# CurrentSource.net
KiCad netlist of a schematic drawn in Altium Designer
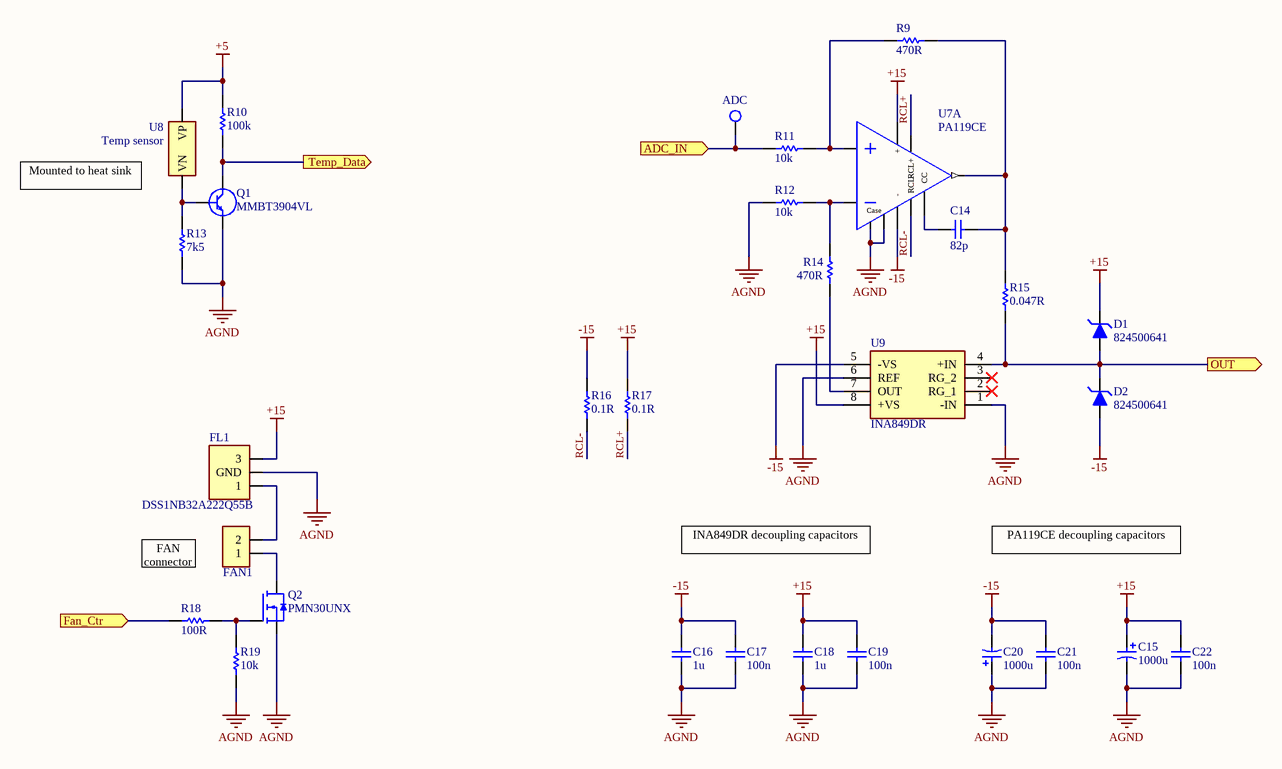
[diagram p0: CurrentSource.SchDoc]

(export (version "E")
  (design (tool "Eeschema 10.0.6"))
  (components
    (comp (ref "C14")
      (value "82p")
      (footprint "Cap_0603_MD_outline")
      (description "Capacitor")
      (fields (field (name "MPN") "GQM1875C2E820JB12D"))
      (libsource (lib "LibPassive") (part "Capacitor"))
    )
    (comp (ref "C15")
      (value "1000u")
      (footprint "CAPAE1350X1400N")
      (description "Aluminium Electrolytic Capacitor")
      (fields (field (name "MPN") "EEE-FK1E102AQ"))
      (libsource (lib "LibPassive") (part "Capacitor Electrolytic"))
    )
    (comp (ref "C16")
      (value "1u")
      (footprint "Cap_0805_MD_outline")
      (description "Capacitor")
      (fields (field (name "MPN") "GCJ21BR71H105KA01L"))
      (libsource (lib "LibPassive") (part "Capacitor"))
    )
    (comp (ref "C17")
      (value "100n")
      (footprint "Cap_0603_MD_outline")
      (description "Capacitor")
      (fields (field (name "MPN") "GRM188R72A104KA35"))
      (libsource (lib "LibPassive") (part "Capacitor"))
    )
    (comp (ref "C18")
      (value "1u")
      (footprint "Cap_0805_MD_outline")
      (description "Capacitor")
      (fields (field (name "MPN") "GCJ21BR71H105KA01L"))
      (libsource (lib "LibPassive") (part "Capacitor"))
    )
    (comp (ref "C19")
      (value "100n")
      (footprint "Cap_0603_MD_outline")
      (description "Capacitor")
      (fields (field (name "MPN") "GRM188R72A104KA35"))
      (libsource (lib "LibPassive") (part "Capacitor"))
    )
    (comp (ref "C20")
      (value "1000u")
      (footprint "CAPAE1350X1400N")
      (description "Aluminium Electrolytic Capacitor")
      (fields (field (name "MPN") "EEE-FK1E102AQ"))
      (libsource (lib "LibPassive") (part "Capacitor Electrolytic"))
    )
    (comp (ref "C21")
      (value "100n")
      (footprint "Cap_0603_MD_outline")
      (description "Capacitor")
      (fields (field (name "MPN") "GRM188R72A104KA35"))
      (libsource (lib "LibPassive") (part "Capacitor"))
    )
    (comp (ref "C22")
      (value "100n")
      (footprint "Cap_0603_MD_outline")
      (description "Capacitor")
      (fields (field (name "MPN") "GRM188R72A104KA35"))
      (libsource (lib "LibPassive") (part "Capacitor"))
    )
    (comp (ref "D1")
      (value "824500641")
      (footprint "DIOM5127X250N")
      (description "TVS Diode")
      (libsource (lib "Library") (part "824500641"))
    )
    (comp (ref "D2")
      (value "824500641")
      (footprint "DIOM5127X250N")
      (description "TVS Diode")
      (libsource (lib "Library") (part "824500641"))
    )
    (comp (ref "FAN1")
      (value "~")
      (footprint "Pads_2")
      (description "2 Pads")
      (libsource (lib "Schlib") (part "Pads_2"))
    )
    (comp (ref "FL1")
      (value "DSS1NB32A222Q55B")
      (footprint "DSS1NB32A223Q91A")
      (description "EMIFilter")
      (libsource (lib "Library") (part "DSS1NB32A222Q55B"))
    )
    (comp (ref "Q1")
      (value "MMBT3904VL")
      (footprint "SOT95P230X110-3N")
      (description "Transistor BJT NPN")
      (libsource (lib "Library") (part "MMBT3904VL"))
    )
    (comp (ref "Q2")
      (value "PMN30UNX")
      (footprint "SOT95P275X110-6N")
      (description "Transistor MOSFET N-Channel")
      (libsource (lib "Schlib") (part "PMN30UNX"))
    )
    (comp (ref "R9")
      (value "470R")
      (footprint "Res_0603_MD_outline")
      (description "Resistor")
      (fields (field (name "MPN") "MCT0603MD4700BP100"))
      (libsource (lib "LibPassive") (part "Resistor"))
    )
    (comp (ref "R10")
      (value "100k")
      (footprint "Res_0603_MD_outline")
      (description "Resistor")
      (fields (field (name "MPN") "CRCW0603100KFKEAC"))
      (libsource (lib "LibPassive") (part "Resistor"))
    )
    (comp (ref "R11")
      (value "10k")
      (footprint "Res_0603_MD_outline")
      (description "Resistor")
      (fields (field (name "MPN") "MCT06030E1002BP100"))
      (libsource (lib "LibPassive") (part "Resistor"))
    )
    (comp (ref "R12")
      (value "10k")
      (footprint "Res_0603_MD_outline")
      (description "Resistor")
      (fields (field (name "MPN") "MCT06030E1002BP100"))
      (libsource (lib "LibPassive") (part "Resistor"))
    )
    (comp (ref "R13")
      (value "7k5")
      (footprint "Res_0603_MD_outline")
      (description "Resistor")
      (fields (field (name "MPN") "CRCW06037K50FKEA"))
      (libsource (lib "LibPassive") (part "Resistor"))
    )
    (comp (ref "R14")
      (value "470R")
      (footprint "Res_0603_MD_outline")
      (description "Resistor")
      (fields (field (name "MPN") "MCT0603MD4700BP100"))
      (libsource (lib "LibPassive") (part "Resistor"))
    )
    (comp (ref "R15")
      (value "0.047R")
      (footprint "Res_2512")
      (description "Resistor")
      (fields (field (name "MPN") "GMR100HTBFQR047"))
      (libsource (lib "LibPassive") (part "Shunt"))
    )
    (comp (ref "R16")
      (value "0.1R")
      (footprint "Res_0603_MD_outline")
      (description "Resistor")
      (fields (field (name "MPN") "RCWE0603R100FNEA"))
      (libsource (lib "LibPassive") (part "Resistor"))
    )
    (comp (ref "R17")
      (value "0.1R")
      (footprint "Res_0603_MD_outline")
      (description "Resistor")
      (fields (field (name "MPN") "RCWE0603R100FNEA"))
      (libsource (lib "LibPassive") (part "Resistor"))
    )
    (comp (ref "R18")
      (value "100R")
      (footprint "Res_0603_MD_outline")
      (description "Resistor")
      (fields (field (name "MPN") "CRCW0603100RFKEAHP"))
      (libsource (lib "LibPassive") (part "Resistor"))
    )
    (comp (ref "R19")
      (value "10k")
      (footprint "Res_0603_MD_outline")
      (description "Resistor")
      (fields (field (name "MPN") "CRCW060310K0FKEAC"))
      (libsource (lib "LibPassive") (part "Resistor"))
    )
    (comp (ref "TP8")
      (value "ADC")
      (footprint "TP_SQ40")
      (description "Test point")
      (libsource (lib "Library") (part "TestPoint"))
    )
    (comp (ref "U7")
      (value "PA119CE")
      (footprint "PA119CE")
      (description "Op Amp")
      (libsource (lib "Library") (part "PA119CE"))
    )
    (comp (ref "U8")
      (value "Temp sensor")
      (footprint "TO-92S")
      (description "Temperature sensor, Pulse Train Interface")
      (fields (field (name "MPN") "LMT01LPGM"))
      (libsource (lib "Schlib") (part "LMT01LPGM"))
    )
    (comp (ref "U9")
      (value "INA849DR")
      (footprint "SOIC127P600X175-8N")
      (description "Instrumental Amplifier")
      (libsource (lib "Library") (part "INA849DR"))
    )
  )
  (nets
    (net (code "1") (name "+5") (class "Default")
      (node (ref "R10") (pin "2") (pinfunction "2_2") (pintype "passive"))
      (node (ref "U8") (pin "2") (pinfunction "VP_2") (pintype "passive"))
    )
    (net (code "2") (name "+15") (class "Default")
      (node (ref "C15") (pin "1") (pinfunction "1_1") (pintype "passive"))
      (node (ref "C18") (pin "2") (pinfunction "2_2") (pintype "passive"))
      (node (ref "C19") (pin "2") (pinfunction "2_2") (pintype "passive"))
      (node (ref "C22") (pin "2") (pinfunction "2_2") (pintype "passive"))
      (node (ref "D1") (pin "1") (pinfunction "K_1") (pintype "passive"))
      (node (ref "FL1") (pin "3") (pinfunction "3_3") (pintype "passive"))
      (node (ref "R17") (pin "2") (pinfunction "2_2") (pintype "passive"))
      (node (ref "U7") (pin "3") (pinfunction "+_3") (pintype "passive"))
      (node (ref "U9") (pin "8") (pinfunction "+VS_8") (pintype "passive"))
    )
    (net (code "3") (name "-15") (class "Default")
      (node (ref "C16") (pin "2") (pinfunction "2_2") (pintype "passive"))
      (node (ref "C17") (pin "2") (pinfunction "2_2") (pintype "passive"))
      (node (ref "C20") (pin "2") (pinfunction "2_2") (pintype "passive"))
      (node (ref "C21") (pin "2") (pinfunction "2_2") (pintype "passive"))
      (node (ref "D2") (pin "2") (pinfunction "A_2") (pintype "passive"))
      (node (ref "R16") (pin "2") (pinfunction "2_2") (pintype "passive"))
      (node (ref "U7") (pin "6") (pinfunction "-_6") (pintype "passive"))
      (node (ref "U9") (pin "5") (pinfunction "-VS_5") (pintype "passive"))
    )
    (net (code "4") (name "/ADC_IN") (class "Default")
      (node (ref "R11") (pin "1") (pinfunction "1_1") (pintype "passive"))
      (node (ref "TP8") (pin "1") (pintype "passive"))
    )
    (net (code "5") (name "/Fan_Ctr") (class "Default")
      (node (ref "R18") (pin "2") (pinfunction "2_2") (pintype "passive"))
    )
    (net (code "6") (name "/OUT") (class "Default")
      (node (ref "D1") (pin "2") (pinfunction "A_2") (pintype "passive"))
      (node (ref "D2") (pin "1") (pinfunction "K_1") (pintype "passive"))
      (node (ref "R15") (pin "1") (pinfunction "1_1") (pintype "passive"))
      (node (ref "U9") (pin "4") (pinfunction "+IN_4") (pintype "passive"))
    )
    (net (code "7") (name "/RCL+") (class "Default")
      (node (ref "R17") (pin "1") (pinfunction "1_1") (pintype "passive"))
      (node (ref "U7") (pin "2") (pinfunction "RCL+_2") (pintype "passive"))
    )
    (net (code "8") (name "/RCL-") (class "Default")
      (node (ref "R16") (pin "1") (pinfunction "1_1") (pintype "passive"))
      (node (ref "U7") (pin "7") (pinfunction "RCL-_7") (pintype "passive"))
    )
    (net (code "9") (name "/Temp_Data") (class "Default")
      (node (ref "Q1") (pin "3") (pinfunction "C_3") (pintype "passive"))
      (node (ref "R10") (pin "1") (pinfunction "1_1") (pintype "passive"))
    )
    (net (code "10") (name "AGND") (class "Default")
      (node (ref "C15") (pin "2") (pinfunction "2_2") (pintype "passive"))
      (node (ref "C16") (pin "1") (pinfunction "1_1") (pintype "passive"))
      (node (ref "C17") (pin "1") (pinfunction "1_1") (pintype "passive"))
      (node (ref "C18") (pin "1") (pinfunction "1_1") (pintype "passive"))
      (node (ref "C19") (pin "1") (pinfunction "1_1") (pintype "passive"))
      (node (ref "C20") (pin "1") (pinfunction "1_1") (pintype "passive"))
      (node (ref "C21") (pin "1") (pinfunction "1_1") (pintype "passive"))
      (node (ref "C22") (pin "1") (pinfunction "1_1") (pintype "passive"))
      (node (ref "FL1") (pin "2") (pinfunction "GND_2") (pintype "passive"))
      (node (ref "Q1") (pin "2") (pinfunction "E_2") (pintype "passive"))
      (node (ref "Q2") (pin "4") (pinfunction "S_4") (pintype "passive"))
      (node (ref "R12") (pin "1") (pinfunction "1_1") (pintype "passive"))
      (node (ref "R13") (pin "1") (pinfunction "1_1") (pintype "passive"))
      (node (ref "R19") (pin "1") (pinfunction "1_1") (pintype "passive"))
      (node (ref "U7") (pin "MH1") (pinfunction "MH1_MH1") (pintype "passive"))
      (node (ref "U7") (pin "MH2") (pinfunction "MH2_MH2") (pintype "passive"))
      (node (ref "U9") (pin "1") (pinfunction "-IN_1") (pintype "passive"))
      (node (ref "U9") (pin "6") (pinfunction "REF_6") (pintype "passive"))
    )
    (net (code "11") (name "Net-(FAN1-Pad2)") (class "Default")
      (node (ref "FAN1") (pin "2") (pinfunction "2_2") (pintype "passive"))
      (node (ref "FL1") (pin "1") (pinfunction "1_1") (pintype "passive"))
    )
    (net (code "12") (name "Net-(Q1-B)") (class "Default")
      (node (ref "Q1") (pin "1") (pinfunction "B_1") (pintype "passive"))
      (node (ref "R13") (pin "2") (pinfunction "2_2") (pintype "passive"))
      (node (ref "U8") (pin "1") (pinfunction "VN_1") (pintype "passive"))
    )
    (net (code "13") (name "Net-(Q2-D)") (class "Default")
      (node (ref "FAN1") (pin "1") (pinfunction "1_1") (pintype "passive"))
      (node (ref "Q2") (pin "1") (pinfunction "D_1") (pintype "passive"))
    )
    (net (code "14") (name "Net-(Q2-G)") (class "Default")
      (node (ref "Q2") (pin "3") (pinfunction "G_3") (pintype "passive"))
      (node (ref "R18") (pin "1") (pinfunction "1_1") (pintype "passive"))
      (node (ref "R19") (pin "2") (pinfunction "2_2") (pintype "passive"))
    )
    (net (code "15") (name "Net-(U7A-+IN)") (class "Default")
      (node (ref "R11") (pin "2") (pinfunction "2_2") (pintype "passive"))
      (node (ref "R9") (pin "1") (pinfunction "1_1") (pintype "passive"))
      (node (ref "U7") (pin "4") (pinfunction "+IN_4") (pintype "passive"))
    )
    (net (code "16") (name "Net-(U7A--IN)") (class "Default")
      (node (ref "R12") (pin "2") (pinfunction "2_2") (pintype "passive"))
      (node (ref "R14") (pin "2") (pinfunction "2_2") (pintype "passive"))
      (node (ref "U7") (pin "5") (pinfunction "-IN_5") (pintype "passive"))
    )
    (net (code "17") (name "Net-(U7A-CC)") (class "Default")
      (node (ref "C14") (pin "2") (pinfunction "2_2") (pintype "passive"))
      (node (ref "U7") (pin "8") (pinfunction "CC_8") (pintype "passive"))
    )
    (net (code "18") (name "Net-(U7A-OUT)") (class "Default")
      (node (ref "C14") (pin "1") (pinfunction "1_1") (pintype "passive"))
      (node (ref "R15") (pin "2") (pinfunction "2_2") (pintype "passive"))
      (node (ref "R9") (pin "2") (pinfunction "2_2") (pintype "passive"))
      (node (ref "U7") (pin "1") (pinfunction "OUT_1") (pintype "output"))
    )
    (net (code "19") (name "Net-(U9-OUT)") (class "Default")
      (node (ref "R14") (pin "1") (pinfunction "1_1") (pintype "passive"))
      (node (ref "U9") (pin "7") (pinfunction "OUT_7") (pintype "passive"))
    )
    (net (code "20") (name "unconnected-(U9-RG_1-Pad2)") (class "Default")
      (node (ref "U9") (pin "2") (pinfunction "RG_1_2") (pintype "passive+no_connect"))
    )
    (net (code "21") (name "unconnected-(U9-RG_2-Pad3)") (class "Default")
      (node (ref "U9") (pin "3") (pinfunction "RG_2_3") (pintype "passive+no_connect"))
    )
  )
)
